# Wemos_GYBMEP.net
KiCad netlist of a schematic drawn in EAGLE
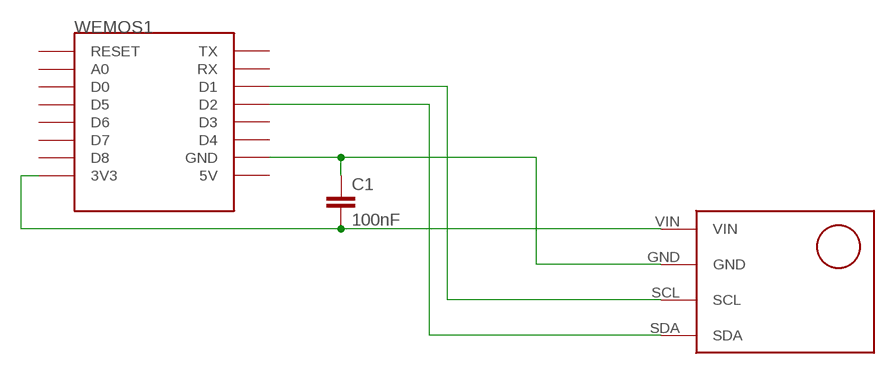
[diagram p0: schematic, sheet 1]

(export (version "E")
  (design (tool "Eeschema 10.0.6"))
  (components
    (comp (ref "C1")
      (value "100nF")
      (footprint "eagle-import:C5B2.5")
      (libsource (lib "eagle-import") (part "C-EU"))
    )
    (comp (ref "U$1")
      (value "GYBMEP")
      (footprint "eagle-import:GYBMEP")
      (libsource (lib "eagle-import") (part "GYBMEP"))
    )
    (comp (ref "WEMOS1")
      (value "WEMOS-D1-MINI")
      (footprint "eagle-import:WEMOS-D1-MINI")
      (libsource (lib "eagle-import") (part "WEMOS-D1-MINI"))
    )
  )
  (nets
    (net (code "1") (name "Net-(C1-Pad1)") (class "Default")
      (node (ref "C1") (pin "1") (pinfunction "1_1") (pintype "passive"))
      (node (ref "U$1") (pin "GND") (pinfunction "GND_GND") (pintype "bidirectional"))
      (node (ref "WEMOS1") (pin "GND") (pinfunction "GND_GND") (pintype "bidirectional"))
    )
    (net (code "2") (name "Net-(C1-Pad2)") (class "Default")
      (node (ref "C1") (pin "2") (pinfunction "2_2") (pintype "passive"))
      (node (ref "U$1") (pin "VIN") (pinfunction "VIN_VIN") (pintype "bidirectional"))
      (node (ref "WEMOS1") (pin "3V3") (pinfunction "3V3_3V3") (pintype "bidirectional"))
    )
    (net (code "3") (name "Net-(U$1-PadSCL)") (class "Default")
      (node (ref "U$1") (pin "SCL") (pinfunction "SCL_SCL") (pintype "bidirectional"))
      (node (ref "WEMOS1") (pin "D1") (pinfunction "D1_D1") (pintype "bidirectional"))
    )
    (net (code "4") (name "Net-(U$1-PadSDA)") (class "Default")
      (node (ref "U$1") (pin "SDA") (pinfunction "SDA_SDA") (pintype "bidirectional"))
      (node (ref "WEMOS1") (pin "D2") (pinfunction "D2_D2") (pintype "bidirectional"))
    )
    (net (code "5") (name "unconnected-(WEMOS1-Pad5V)") (class "Default")
      (node (ref "WEMOS1") (pin "5V") (pinfunction "5V_5V") (pintype "bidirectional"))
    )
    (net (code "6") (name "unconnected-(WEMOS1-PadA0)") (class "Default")
      (node (ref "WEMOS1") (pin "A0") (pinfunction "A0_A0") (pintype "bidirectional"))
    )
    (net (code "7") (name "unconnected-(WEMOS1-PadD0)") (class "Default")
      (node (ref "WEMOS1") (pin "D0") (pinfunction "D0_D0") (pintype "bidirectional"))
    )
    (net (code "8") (name "unconnected-(WEMOS1-PadD3)") (class "Default")
      (node (ref "WEMOS1") (pin "D3") (pinfunction "D3_D3") (pintype "bidirectional"))
    )
    (net (code "9") (name "unconnected-(WEMOS1-PadD4)") (class "Default")
      (node (ref "WEMOS1") (pin "D4") (pinfunction "D4_D4") (pintype "bidirectional"))
    )
    (net (code "10") (name "unconnected-(WEMOS1-PadD5)") (class "Default")
      (node (ref "WEMOS1") (pin "D5") (pinfunction "D5_D5") (pintype "bidirectional"))
    )
    (net (code "11") (name "unconnected-(WEMOS1-PadD6)") (class "Default")
      (node (ref "WEMOS1") (pin "D6") (pinfunction "D6_D6") (pintype "bidirectional"))
    )
    (net (code "12") (name "unconnected-(WEMOS1-PadD7)") (class "Default")
      (node (ref "WEMOS1") (pin "D7") (pinfunction "D7_D7") (pintype "bidirectional"))
    )
    (net (code "13") (name "unconnected-(WEMOS1-PadD8)") (class "Default")
      (node (ref "WEMOS1") (pin "D8") (pinfunction "D8_D8") (pintype "bidirectional"))
    )
    (net (code "14") (name "unconnected-(WEMOS1-PadRESET)") (class "Default")
      (node (ref "WEMOS1") (pin "RESET") (pinfunction "RESET_RESET") (pintype "bidirectional"))
    )
    (net (code "15") (name "unconnected-(WEMOS1-PadRX)") (class "Default")
      (node (ref "WEMOS1") (pin "RX") (pinfunction "RX_RX") (pintype "bidirectional"))
    )
    (net (code "16") (name "unconnected-(WEMOS1-PadTX)") (class "Default")
      (node (ref "WEMOS1") (pin "TX") (pinfunction "TX_TX") (pintype "bidirectional"))
    )
  )
)
